# Micro.net
KiCad netlist of a schematic drawn in Altium Designer
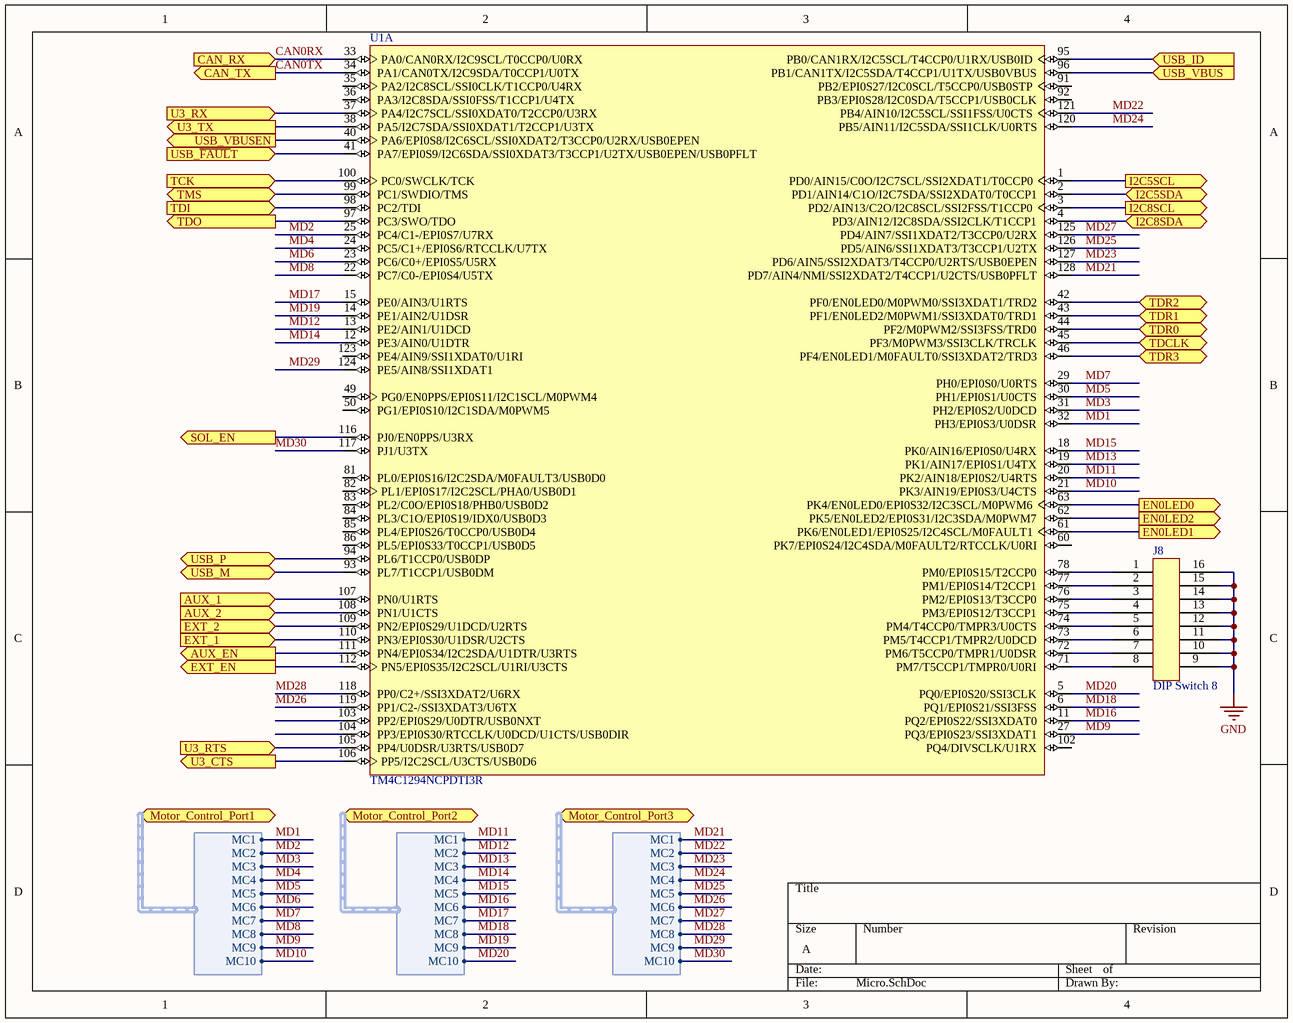
[diagram p0: Micro.SchDoc]

(export (version "E")
  (design (tool "Eeschema 10.0.6"))
  (components
    (comp (ref "J8") (value "DIP Switch 8") (footprint "DIP8") (libsource (lib "HSBNE-MAIN") (part "DIP8")))
    (comp (ref "U1")
      (value "TM4C1294NCPDTI3R")
      (footprint "TI-PDT128_M")
      (fields (field (name "MANUFACTURER") "Texas Instruments"))
      (libsource (lib "Altium Inc") (part "TI-TM4C1294NCPDT-128"))
    )
  )
  (nets
    (net (code "2") (name "/AUX_1") (class "Default")
      (node (ref "U1") (pin "107") (pinfunction "PN0/U1RTS_107") (pintype "bidirectional"))
    )
    (net (code "3") (name "/AUX_2") (class "Default")
      (node (ref "U1") (pin "108") (pinfunction "PN1/U1CTS_108") (pintype "bidirectional"))
    )
    (net (code "4") (name "/AUX_EN") (class "Default")
      (node (ref "U1") (pin "111") (pinfunction "PN4/EPI0S34/I2C2SDA/U1DTR/U3RTS_111") (pintype "bidirectional"))
    )
    (net (code "5") (name "/CAN0RX") (class "Default")
      (node (ref "U1") (pin "33") (pinfunction "PA0/CAN0RX/I2C9SCL/T0CCP0/U0RX_33") (pintype "bidirectional"))
    )
    (net (code "6") (name "/CAN0TX") (class "Default")
      (node (ref "U1") (pin "34") (pinfunction "PA1/CAN0TX/I2C9SDA/T0CCP1/U0TX_34") (pintype "bidirectional"))
    )
    (net (code "7") (name "/EN0LED0") (class "Default")
      (node (ref "U1") (pin "63") (pinfunction "PK4/EN0LED0/EPI0S32/I2C3SCL/M0PWM6_63") (pintype "bidirectional"))
    )
    (net (code "8") (name "/EN0LED1") (class "Default")
      (node (ref "U1") (pin "61") (pinfunction "PK6/EN0LED1/EPI0S25/I2C4SCL/M0FAULT1_61") (pintype "bidirectional"))
    )
    (net (code "9") (name "/EN0LED2") (class "Default")
      (node (ref "U1") (pin "62") (pinfunction "PK5/EN0LED2/EPI0S31/I2C3SDA/M0PWM7_62") (pintype "bidirectional"))
    )
    (net (code "10") (name "/EXT_1") (class "Default")
      (node (ref "U1") (pin "110") (pinfunction "PN3/EPI0S30/U1DSR/U2CTS_110") (pintype "bidirectional"))
    )
    (net (code "11") (name "/EXT_2") (class "Default")
      (node (ref "U1") (pin "109") (pinfunction "PN2/EPI0S29/U1DCD/U2RTS_109") (pintype "bidirectional"))
    )
    (net (code "12") (name "/EXT_EN") (class "Default")
      (node (ref "U1") (pin "112") (pinfunction "PN5/EPI0S35/I2C2SCL/U1RI/U3CTS_112") (pintype "bidirectional"))
    )
    (net (code "13") (name "/I2C5SCL") (class "Default")
      (node (ref "U1") (pin "1") (pinfunction "PD0/AIN15/C0O/I2C7SCL/SSI2XDAT1/T0CCP0_1") (pintype "bidirectional"))
    )
    (net (code "14") (name "/I2C5SDA") (class "Default")
      (node (ref "U1") (pin "2") (pinfunction "PD1/AIN14/C1O/I2C7SDA/SSI2XDAT0/T0CCP1_2") (pintype "bidirectional"))
    )
    (net (code "15") (name "/I2C8SCL") (class "Default")
      (node (ref "U1") (pin "3") (pinfunction "PD2/AIN13/C2O/I2C8SCL/SSI2FSS/T1CCP0_3") (pintype "bidirectional"))
    )
    (net (code "16") (name "/I2C8SDA") (class "Default")
      (node (ref "U1") (pin "4") (pinfunction "PD3/AIN12/I2C8SDA/SSI2CLK/T1CCP1_4") (pintype "bidirectional"))
    )
    (net (code "17") (name "/MD1") (class "Default")
      (node (ref "U1") (pin "32") (pinfunction "PH3/EPI0S3/U0DSR_32") (pintype "bidirectional"))
    )
    (net (code "18") (name "/MD2") (class "Default")
      (node (ref "U1") (pin "25") (pinfunction "PC4/C1-/EPI0S7/U7RX_25") (pintype "bidirectional"))
    )
    (net (code "19") (name "/MD3") (class "Default")
      (node (ref "U1") (pin "31") (pinfunction "PH2/EPI0S2/U0DCD_31") (pintype "bidirectional"))
    )
    (net (code "20") (name "/MD4") (class "Default")
      (node (ref "U1") (pin "24") (pinfunction "PC5/C1+/EPI0S6/RTCCLK/U7TX_24") (pintype "bidirectional"))
    )
    (net (code "21") (name "/MD5") (class "Default")
      (node (ref "U1") (pin "30") (pinfunction "PH1/EPI0S1/U0CTS_30") (pintype "bidirectional"))
    )
    (net (code "22") (name "/MD6") (class "Default")
      (node (ref "U1") (pin "23") (pinfunction "PC6/C0+/EPI0S5/U5RX_23") (pintype "bidirectional"))
    )
    (net (code "23") (name "/MD7") (class "Default")
      (node (ref "U1") (pin "29") (pinfunction "PH0/EPI0S0/U0RTS_29") (pintype "bidirectional"))
    )
    (net (code "24") (name "/MD8") (class "Default")
      (node (ref "U1") (pin "22") (pinfunction "PC7/C0-/EPI0S4/U5TX_22") (pintype "bidirectional"))
    )
    (net (code "25") (name "/MD9") (class "Default")
      (node (ref "U1") (pin "27") (pinfunction "PQ3/EPI0S23/SSI3XDAT1_27") (pintype "bidirectional"))
    )
    (net (code "26") (name "/MD10") (class "Default")
      (node (ref "U1") (pin "21") (pinfunction "PK3/AIN19/EPI0S3/U4CTS_21") (pintype "bidirectional"))
    )
    (net (code "27") (name "/MD11") (class "Default")
      (node (ref "U1") (pin "20") (pinfunction "PK2/AIN18/EPI0S2/U4RTS_20") (pintype "bidirectional"))
    )
    (net (code "28") (name "/MD12") (class "Default")
      (node (ref "U1") (pin "13") (pinfunction "PE2/AIN1/U1DCD_13") (pintype "bidirectional"))
    )
    (net (code "29") (name "/MD13") (class "Default")
      (node (ref "U1") (pin "19") (pinfunction "PK1/AIN17/EPI0S1/U4TX_19") (pintype "bidirectional"))
    )
    (net (code "30") (name "/MD14") (class "Default")
      (node (ref "U1") (pin "12") (pinfunction "PE3/AIN0/U1DTR_12") (pintype "bidirectional"))
    )
    (net (code "31") (name "/MD15") (class "Default")
      (node (ref "U1") (pin "18") (pinfunction "PK0/AIN16/EPI0S0/U4RX_18") (pintype "bidirectional"))
    )
    (net (code "32") (name "/MD16") (class "Default")
      (node (ref "U1") (pin "11") (pinfunction "PQ2/EPI0S22/SSI3XDAT0_11") (pintype "bidirectional"))
    )
    (net (code "33") (name "/MD17") (class "Default")
      (node (ref "U1") (pin "15") (pinfunction "PE0/AIN3/U1RTS_15") (pintype "bidirectional"))
    )
    (net (code "34") (name "/MD18") (class "Default")
      (node (ref "U1") (pin "6") (pinfunction "PQ1/EPI0S21/SSI3FSS_6") (pintype "bidirectional"))
    )
    (net (code "35") (name "/MD19") (class "Default")
      (node (ref "U1") (pin "14") (pinfunction "PE1/AIN2/U1DSR_14") (pintype "bidirectional"))
    )
    (net (code "36") (name "/MD20") (class "Default")
      (node (ref "U1") (pin "5") (pinfunction "PQ0/EPI0S20/SSI3CLK_5") (pintype "bidirectional"))
    )
    (net (code "37") (name "/MD21") (class "Default")
      (node (ref "U1") (pin "128") (pinfunction "PD7/AIN4/NMI/SSI2XDAT2/T4CCP1/U2CTS/USB0PFLT_128") (pintype "bidirectional"))
    )
    (net (code "38") (name "/MD22") (class "Default")
      (node (ref "U1") (pin "121") (pinfunction "PB4/AIN10/I2C5SCL/SSI1FSS/U0CTS_121") (pintype "bidirectional"))
    )
    (net (code "39") (name "/MD23") (class "Default")
      (node (ref "U1") (pin "127") (pinfunction "PD6/AIN5/SSI2XDAT3/T4CCP0/U2RTS/USB0EPEN_127") (pintype "bidirectional"))
    )
    (net (code "40") (name "/MD24") (class "Default")
      (node (ref "U1") (pin "120") (pinfunction "PB5/AIN11/I2C5SDA/SSI1CLK/U0RTS_120") (pintype "bidirectional"))
    )
    (net (code "41") (name "/MD25") (class "Default")
      (node (ref "U1") (pin "126") (pinfunction "PD5/AIN6/SSI1XDAT3/T3CCP1/U2TX_126") (pintype "bidirectional"))
    )
    (net (code "42") (name "/MD26") (class "Default")
      (node (ref "U1") (pin "119") (pinfunction "PP1/C2-/SSI3XDAT3/U6TX_119") (pintype "bidirectional"))
    )
    (net (code "43") (name "/MD27") (class "Default")
      (node (ref "U1") (pin "125") (pinfunction "PD4/AIN7/SSI1XDAT2/T3CCP0/U2RX_125") (pintype "bidirectional"))
    )
    (net (code "44") (name "/MD28") (class "Default")
      (node (ref "U1") (pin "118") (pinfunction "PP0/C2+/SSI3XDAT2/U6RX_118") (pintype "bidirectional"))
    )
    (net (code "45") (name "/MD29") (class "Default")
      (node (ref "U1") (pin "124") (pinfunction "PE5/AIN8/SSI1XDAT1_124") (pintype "bidirectional"))
    )
    (net (code "46") (name "/MD30") (class "Default")
      (node (ref "U1") (pin "117") (pinfunction "PJ1/U3TX_117") (pintype "bidirectional"))
    )
    (net (code "47") (name "/SOL_EN") (class "Default")
      (node (ref "U1") (pin "116") (pinfunction "PJ0/EN0PPS/U3RX_116") (pintype "bidirectional"))
    )
    (net (code "48") (name "/TCK") (class "Default")
      (node (ref "U1") (pin "100") (pinfunction "PC0/SWCLK/TCK_100") (pintype "bidirectional"))
    )
    (net (code "49") (name "/TDCLK") (class "Default")
      (node (ref "U1") (pin "45") (pinfunction "PF3/M0PWM3/SSI3CLK/TRCLK_45") (pintype "bidirectional"))
    )
    (net (code "50") (name "/TDI") (class "Default")
      (node (ref "U1") (pin "98") (pinfunction "PC2/TDI_98") (pintype "bidirectional"))
    )
    (net (code "51") (name "/TDO") (class "Default")
      (node (ref "U1") (pin "97") (pinfunction "PC3/SWO/TDO_97") (pintype "bidirectional"))
    )
    (net (code "52") (name "/TDR0") (class "Default")
      (node (ref "U1") (pin "44") (pinfunction "PF2/M0PWM2/SSI3FSS/TRD0_44") (pintype "bidirectional"))
    )
    (net (code "53") (name "/TDR1") (class "Default")
      (node (ref "U1") (pin "43") (pinfunction "PF1/EN0LED2/M0PWM1/SSI3XDAT0/TRD1_43") (pintype "bidirectional"))
    )
    (net (code "54") (name "/TDR2") (class "Default")
      (node (ref "U1") (pin "42") (pinfunction "PF0/EN0LED0/M0PWM0/SSI3XDAT1/TRD2_42") (pintype "bidirectional"))
    )
    (net (code "55") (name "/TDR3") (class "Default")
      (node (ref "U1") (pin "46") (pinfunction "PF4/EN0LED1/M0FAULT0/SSI3XDAT2/TRD3_46") (pintype "bidirectional"))
    )
    (net (code "56") (name "/TMS") (class "Default")
      (node (ref "U1") (pin "99") (pinfunction "PC1/SWDIO/TMS_99") (pintype "bidirectional"))
    )
    (net (code "57") (name "/U3_CTS") (class "Default")
      (node (ref "U1") (pin "106") (pinfunction "PP5/I2C2SCL/U3CTS/USB0D6_106") (pintype "bidirectional"))
    )
    (net (code "58") (name "/U3_RTS") (class "Default")
      (node (ref "U1") (pin "105") (pinfunction "PP4/U0DSR/U3RTS/USB0D7_105") (pintype "bidirectional"))
    )
    (net (code "59") (name "/U3_RX") (class "Default")
      (node (ref "U1") (pin "37") (pinfunction "PA4/I2C7SCL/SSI0XDAT0/T2CCP0/U3RX_37") (pintype "bidirectional"))
    )
    (net (code "60") (name "/U3_TX") (class "Default")
      (node (ref "U1") (pin "38") (pinfunction "PA5/I2C7SDA/SSI0XDAT1/T2CCP1/U3TX_38") (pintype "bidirectional"))
    )
    (net (code "61") (name "/USB_ID") (class "Default")
      (node (ref "U1") (pin "95") (pinfunction "PB0/CAN1RX/I2C5SCL/T4CCP0/U1RX/USB0ID_95") (pintype "bidirectional"))
    )
    (net (code "62") (name "/USB_M") (class "Default")
      (node (ref "U1") (pin "93") (pinfunction "PL7/T1CCP1/USB0DM_93") (pintype "bidirectional"))
    )
    (net (code "63") (name "/USB_P") (class "Default")
      (node (ref "U1") (pin "94") (pinfunction "PL6/T1CCP0/USB0DP_94") (pintype "bidirectional"))
    )
    (net (code "64") (name "/USB_VBUS") (class "Default")
      (node (ref "U1") (pin "96") (pinfunction "PB1/CAN1TX/I2C5SDA/T4CCP1/U1TX/USB0VBUS_96") (pintype "bidirectional"))
    )
    (net (code "65") (name "/USB_VBUSEN") (class "Default")
      (node (ref "U1") (pin "40") (pinfunction "PA6/EPI0S8/I2C6SCL/SSI0XDAT2/T3CCP0/U2RX/USB0EPEN_40") (pintype "bidirectional"))
    )
    (net (code "66") (name "/USB_~{FAUL}T") (class "Default")
      (node (ref "U1") (pin "41") (pinfunction "PA7/EPI0S9/I2C6SDA/SSI0XDAT3/T3CCP1/U2TX/USB0EPEN/USB0PFLT_41") (pintype "bidirectional"))
    )
    (net (code "68") (name "GND") (class "Default")
      (node (ref "J8") (pin "10") (pinfunction "10_10") (pintype "passive"))
      (node (ref "J8") (pin "11") (pinfunction "11_11") (pintype "passive"))
      (node (ref "J8") (pin "12") (pinfunction "12_12") (pintype "passive"))
      (node (ref "J8") (pin "13") (pinfunction "13_13") (pintype "passive"))
      (node (ref "J8") (pin "14") (pinfunction "14_14") (pintype "passive"))
      (node (ref "J8") (pin "15") (pinfunction "15_15") (pintype "passive"))
      (node (ref "J8") (pin "16") (pinfunction "16_16") (pintype "passive"))
      (node (ref "J8") (pin "9") (pinfunction "9_9") (pintype "passive"))
    )
    (net (code "69") (name "Net-(U1A-PM0{slash}EPI0S15{slash}T2CCP0)") (class "Default")
      (node (ref "J8") (pin "1") (pinfunction "1_1") (pintype "passive"))
      (node (ref "U1") (pin "78") (pinfunction "PM0/EPI0S15/T2CCP0_78") (pintype "bidirectional"))
    )
    (net (code "70") (name "Net-(U1A-PM1{slash}EPI0S14{slash}T2CCP1)") (class "Default")
      (node (ref "J8") (pin "2") (pinfunction "2_2") (pintype "passive"))
      (node (ref "U1") (pin "77") (pinfunction "PM1/EPI0S14/T2CCP1_77") (pintype "bidirectional"))
    )
    (net (code "71") (name "Net-(U1A-PM2{slash}EPI0S13{slash}T3CCP0)") (class "Default")
      (node (ref "J8") (pin "3") (pinfunction "3_3") (pintype "passive"))
      (node (ref "U1") (pin "76") (pinfunction "PM2/EPI0S13/T3CCP0_76") (pintype "bidirectional"))
    )
    (net (code "72") (name "Net-(U1A-PM3{slash}EPI0S12{slash}T3CCP1)") (class "Default")
      (node (ref "J8") (pin "4") (pinfunction "4_4") (pintype "passive"))
      (node (ref "U1") (pin "75") (pinfunction "PM3/EPI0S12/T3CCP1_75") (pintype "bidirectional"))
    )
    (net (code "73") (name "Net-(U1A-PM4{slash}T4CCP0{slash}TMPR3{slash}U0CTS)") (class "Default")
      (node (ref "J8") (pin "5") (pinfunction "5_5") (pintype "passive"))
      (node (ref "U1") (pin "74") (pinfunction "PM4/T4CCP0/TMPR3/U0CTS_74") (pintype "bidirectional"))
    )
    (net (code "74") (name "Net-(U1A-PM5{slash}T4CCP1{slash}TMPR2{slash}U0DCD)") (class "Default")
      (node (ref "J8") (pin "6") (pinfunction "6_6") (pintype "passive"))
      (node (ref "U1") (pin "73") (pinfunction "PM5/T4CCP1/TMPR2/U0DCD_73") (pintype "bidirectional"))
    )
    (net (code "75") (name "Net-(U1A-PM6{slash}T5CCP0{slash}TMPR1{slash}U0DSR)") (class "Default")
      (node (ref "J8") (pin "7") (pinfunction "7_7") (pintype "passive"))
      (node (ref "U1") (pin "72") (pinfunction "PM6/T5CCP0/TMPR1/U0DSR_72") (pintype "bidirectional"))
    )
    (net (code "76") (name "Net-(U1A-PM7{slash}T5CCP1{slash}TMPR0{slash}U0RI)") (class "Default")
      (node (ref "J8") (pin "8") (pinfunction "8_8") (pintype "passive"))
      (node (ref "U1") (pin "71") (pinfunction "PM7/T5CCP1/TMPR0/U0RI_71") (pintype "bidirectional"))
    )
    (net (code "77") (name "unconnected-(U1A-PA2{slash}I2C8SCL{slash}SSI0CLK{slash}T1CCP0{slash}U4RX-Pad35)") (class "Default")
      (node (ref "U1") (pin "35") (pinfunction "PA2/I2C8SCL/SSI0CLK/T1CCP0/U4RX_35") (pintype "bidirectional"))
    )
    (net (code "78") (name "unconnected-(U1A-PA3{slash}I2C8SDA{slash}SSI0FSS{slash}T1CCP1{slash}U4TX-Pad36)") (class "Default")
      (node (ref "U1") (pin "36") (pinfunction "PA3/I2C8SDA/SSI0FSS/T1CCP1/U4TX_36") (pintype "bidirectional"))
    )
    (net (code "79") (name "unconnected-(U1A-PB2{slash}EPI0S27{slash}I2C0SCL{slash}T5CCP0{slash}USB0STP-Pad91)") (class "Default")
      (node (ref "U1") (pin "91") (pinfunction "PB2/EPI0S27/I2C0SCL/T5CCP0/USB0STP_91") (pintype "bidirectional"))
    )
    (net (code "80") (name "unconnected-(U1A-PB3{slash}EPI0S28{slash}I2C0SDA{slash}T5CCP1{slash}USB0CLK-Pad92)") (class "Default")
      (node (ref "U1") (pin "92") (pinfunction "PB3/EPI0S28/I2C0SDA/T5CCP1/USB0CLK_92") (pintype "bidirectional"))
    )
    (net (code "81") (name "unconnected-(U1A-PE4{slash}AIN9{slash}SSI1XDAT0{slash}U1RI-Pad123)") (class "Default")
      (node (ref "U1") (pin "123") (pinfunction "PE4/AIN9/SSI1XDAT0/U1RI_123") (pintype "bidirectional"))
    )
    (net (code "82") (name "unconnected-(U1A-PG0{slash}EN0PPS{slash}EPI0S11{slash}I2C1SCL{slash}M0PWM4-Pad49)") (class "Default")
      (node (ref "U1") (pin "49") (pinfunction "PG0/EN0PPS/EPI0S11/I2C1SCL/M0PWM4_49") (pintype "bidirectional"))
    )
    (net (code "83") (name "unconnected-(U1A-PG1{slash}EPI0S10{slash}I2C1SDA{slash}M0PWM5-Pad50)") (class "Default")
      (node (ref "U1") (pin "50") (pinfunction "PG1/EPI0S10/I2C1SDA/M0PWM5_50") (pintype "bidirectional"))
    )
    (net (code "84") (name "unconnected-(U1A-PK7{slash}EPI0S24{slash}I2C4SDA{slash}M0FAULT2{slash}RTCCLK{slash}U0RI-Pad60)") (class "Default")
      (node (ref "U1") (pin "60") (pinfunction "PK7/EPI0S24/I2C4SDA/M0FAULT2/RTCCLK/U0RI_60") (pintype "bidirectional"))
    )
    (net (code "85") (name "unconnected-(U1A-PL0{slash}EPI0S16{slash}I2C2SDA{slash}M0FAULT3{slash}USB0D0-Pad81)") (class "Default")
      (node (ref "U1") (pin "81") (pinfunction "PL0/EPI0S16/I2C2SDA/M0FAULT3/USB0D0_81") (pintype "bidirectional"))
    )
    (net (code "86") (name "unconnected-(U1A-PL1{slash}EPI0S17{slash}I2C2SCL{slash}PHA0{slash}USB0D1-Pad82)") (class "Default")
      (node (ref "U1") (pin "82") (pinfunction "PL1/EPI0S17/I2C2SCL/PHA0/USB0D1_82") (pintype "bidirectional"))
    )
    (net (code "87") (name "unconnected-(U1A-PL2{slash}C0O{slash}EPI0S18{slash}PHB0{slash}USB0D2-Pad83)") (class "Default")
      (node (ref "U1") (pin "83") (pinfunction "PL2/C0O/EPI0S18/PHB0/USB0D2_83") (pintype "bidirectional"))
    )
    (net (code "88") (name "unconnected-(U1A-PL3{slash}C1O{slash}EPI0S19{slash}IDX0{slash}USB0D3-Pad84)") (class "Default")
      (node (ref "U1") (pin "84") (pinfunction "PL3/C1O/EPI0S19/IDX0/USB0D3_84") (pintype "bidirectional"))
    )
    (net (code "89") (name "unconnected-(U1A-PL4{slash}EPI0S26{slash}T0CCP0{slash}USB0D4-Pad85)") (class "Default")
      (node (ref "U1") (pin "85") (pinfunction "PL4/EPI0S26/T0CCP0/USB0D4_85") (pintype "bidirectional"))
    )
    (net (code "90") (name "unconnected-(U1A-PL5{slash}EPI0S33{slash}T0CCP1{slash}USB0D5-Pad86)") (class "Default")
      (node (ref "U1") (pin "86") (pinfunction "PL5/EPI0S33/T0CCP1/USB0D5_86") (pintype "bidirectional"))
    )
    (net (code "91") (name "unconnected-(U1A-PP2{slash}EPI0S29{slash}U0DTR{slash}USB0NXT-Pad103)") (class "Default")
      (node (ref "U1") (pin "103") (pinfunction "PP2/EPI0S29/U0DTR/USB0NXT_103") (pintype "bidirectional"))
    )
    (net (code "92") (name "unconnected-(U1A-PP3{slash}EPI0S30{slash}RTCCLK{slash}U0DCD{slash}U1CTS{slash}USB0DIR-Pad104)") (class "Default")
      (node (ref "U1") (pin "104") (pinfunction "PP3/EPI0S30/RTCCLK/U0DCD/U1CTS/USB0DIR_104") (pintype "bidirectional"))
    )
    (net (code "93") (name "unconnected-(U1A-PQ4{slash}DIVSCLK{slash}U1RX-Pad102)") (class "Default")
      (node (ref "U1") (pin "102") (pinfunction "PQ4/DIVSCLK/U1RX_102") (pintype "bidirectional"))
    )
  )
)
